# 03-ES7210-MIC.net
KiCad netlist of a schematic drawn in EasyEDA
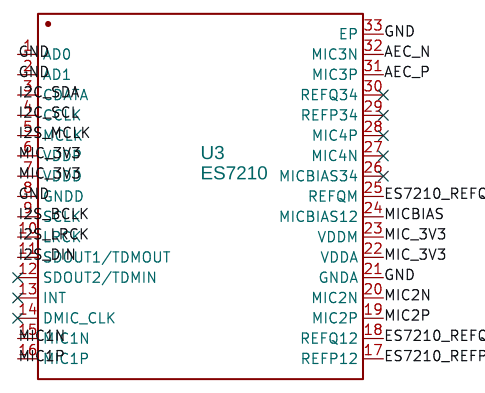
[diagram p0: schematic sheet]

(export (version "E")
  (design (tool "Eeschema 10.0.6"))
  (components
    (comp (ref "U3")
      (value "ES7210")
      (fields (field (name "Manufacturer") "Everest-semi()"))
      (libsource (lib "") (part "Unknown_400.0_300.0"))
    )
  )
  (nets
    (net (code "1") (name "/AEC_N") (class "Default")
      (node (ref "U3") (pin "32") (pinfunction "MIC3N_32") (pintype "unspecified"))
    )
    (net (code "2") (name "/AEC_P") (class "Default")
      (node (ref "U3") (pin "31") (pinfunction "MIC3P_31") (pintype "unspecified"))
    )
    (net (code "3") (name "/ES7210_REFP12") (class "Default")
      (node (ref "U3") (pin "17") (pinfunction "REFP12_17") (pintype "unspecified"))
    )
    (net (code "4") (name "/ES7210_REFQ12") (class "Default")
      (node (ref "U3") (pin "18") (pinfunction "REFQ12_18") (pintype "unspecified"))
    )
    (net (code "5") (name "/ES7210_REFQM") (class "Default")
      (node (ref "U3") (pin "25") (pinfunction "REFQM_25") (pintype "unspecified"))
    )
    (net (code "6") (name "/GND") (class "Default")
      (node (ref "U3") (pin "1") (pinfunction "AD0_1") (pintype "unspecified"))
      (node (ref "U3") (pin "2") (pinfunction "AD1_2") (pintype "unspecified"))
      (node (ref "U3") (pin "21") (pinfunction "GNDA_21") (pintype "unspecified"))
      (node (ref "U3") (pin "33") (pinfunction "EP_33") (pintype "unspecified"))
      (node (ref "U3") (pin "8") (pinfunction "GNDD_8") (pintype "unspecified"))
    )
    (net (code "7") (name "/I2C_SCL") (class "Default")
      (node (ref "U3") (pin "4") (pinfunction "CCLK_4") (pintype "unspecified"))
    )
    (net (code "8") (name "/I2C_SDA") (class "Default")
      (node (ref "U3") (pin "3") (pinfunction "CDATA_3") (pintype "unspecified"))
    )
    (net (code "9") (name "/I2S_BCLK") (class "Default")
      (node (ref "U3") (pin "9") (pinfunction "SCLK_9") (pintype "unspecified"))
    )
    (net (code "10") (name "/I2S_DIN") (class "Default")
      (node (ref "U3") (pin "11") (pinfunction "SDOUT1/TDMOUT_11") (pintype "unspecified"))
    )
    (net (code "11") (name "/I2S_LRCK") (class "Default")
      (node (ref "U3") (pin "10") (pinfunction "LRCK_10") (pintype "unspecified"))
    )
    (net (code "12") (name "/I2S_MCLK") (class "Default")
      (node (ref "U3") (pin "5") (pinfunction "MCLK_5") (pintype "unspecified"))
    )
    (net (code "13") (name "/MIC1N") (class "Default")
      (node (ref "U3") (pin "15") (pinfunction "MIC1N_15") (pintype "unspecified"))
    )
    (net (code "14") (name "/MIC1P") (class "Default")
      (node (ref "U3") (pin "16") (pinfunction "MIC1P_16") (pintype "unspecified"))
    )
    (net (code "15") (name "/MIC2N") (class "Default")
      (node (ref "U3") (pin "20") (pinfunction "MIC2N_20") (pintype "unspecified"))
    )
    (net (code "16") (name "/MIC2P") (class "Default")
      (node (ref "U3") (pin "19") (pinfunction "MIC2P_19") (pintype "unspecified"))
    )
    (net (code "17") (name "/MICBIAS") (class "Default")
      (node (ref "U3") (pin "24") (pinfunction "MICBIAS12_24") (pintype "unspecified"))
    )
    (net (code "18") (name "/MIC_3V3") (class "Default")
      (node (ref "U3") (pin "22") (pinfunction "VDDA_22") (pintype "unspecified"))
      (node (ref "U3") (pin "23") (pinfunction "VDDM_23") (pintype "unspecified"))
      (node (ref "U3") (pin "6") (pinfunction "VDDP_6") (pintype "unspecified"))
      (node (ref "U3") (pin "7") (pinfunction "VDDD_7") (pintype "unspecified"))
    )
    (net (code "19") (name "unconnected-(U3-DMIC_CLK-Pad14)") (class "Default")
      (node (ref "U3") (pin "14") (pinfunction "DMIC_CLK_14") (pintype "unspecified+no_connect"))
    )
    (net (code "20") (name "unconnected-(U3-INT-Pad13)") (class "Default")
      (node (ref "U3") (pin "13") (pinfunction "INT_13") (pintype "unspecified+no_connect"))
    )
    (net (code "21") (name "unconnected-(U3-MIC4N-Pad27)") (class "Default")
      (node (ref "U3") (pin "27") (pinfunction "MIC4N_27") (pintype "unspecified+no_connect"))
    )
    (net (code "22") (name "unconnected-(U3-MIC4P-Pad28)") (class "Default")
      (node (ref "U3") (pin "28") (pinfunction "MIC4P_28") (pintype "unspecified+no_connect"))
    )
    (net (code "23") (name "unconnected-(U3-MICBIAS34-Pad26)") (class "Default")
      (node (ref "U3") (pin "26") (pinfunction "MICBIAS34_26") (pintype "unspecified+no_connect"))
    )
    (net (code "24") (name "unconnected-(U3-REFP34-Pad29)") (class "Default")
      (node (ref "U3") (pin "29") (pinfunction "REFP34_29") (pintype "unspecified+no_connect"))
    )
    (net (code "25") (name "unconnected-(U3-REFQ34-Pad30)") (class "Default")
      (node (ref "U3") (pin "30") (pinfunction "REFQ34_30") (pintype "unspecified+no_connect"))
    )
    (net (code "26") (name "unconnected-(U3-SDOUT2{slash}TDMIN-Pad12)") (class "Default")
      (node (ref "U3") (pin "12") (pinfunction "SDOUT2/TDMIN_12") (pintype "unspecified+no_connect"))
    )
  )
)
